# adapter_v2.net
KiCad netlist of a schematic drawn in EAGLE
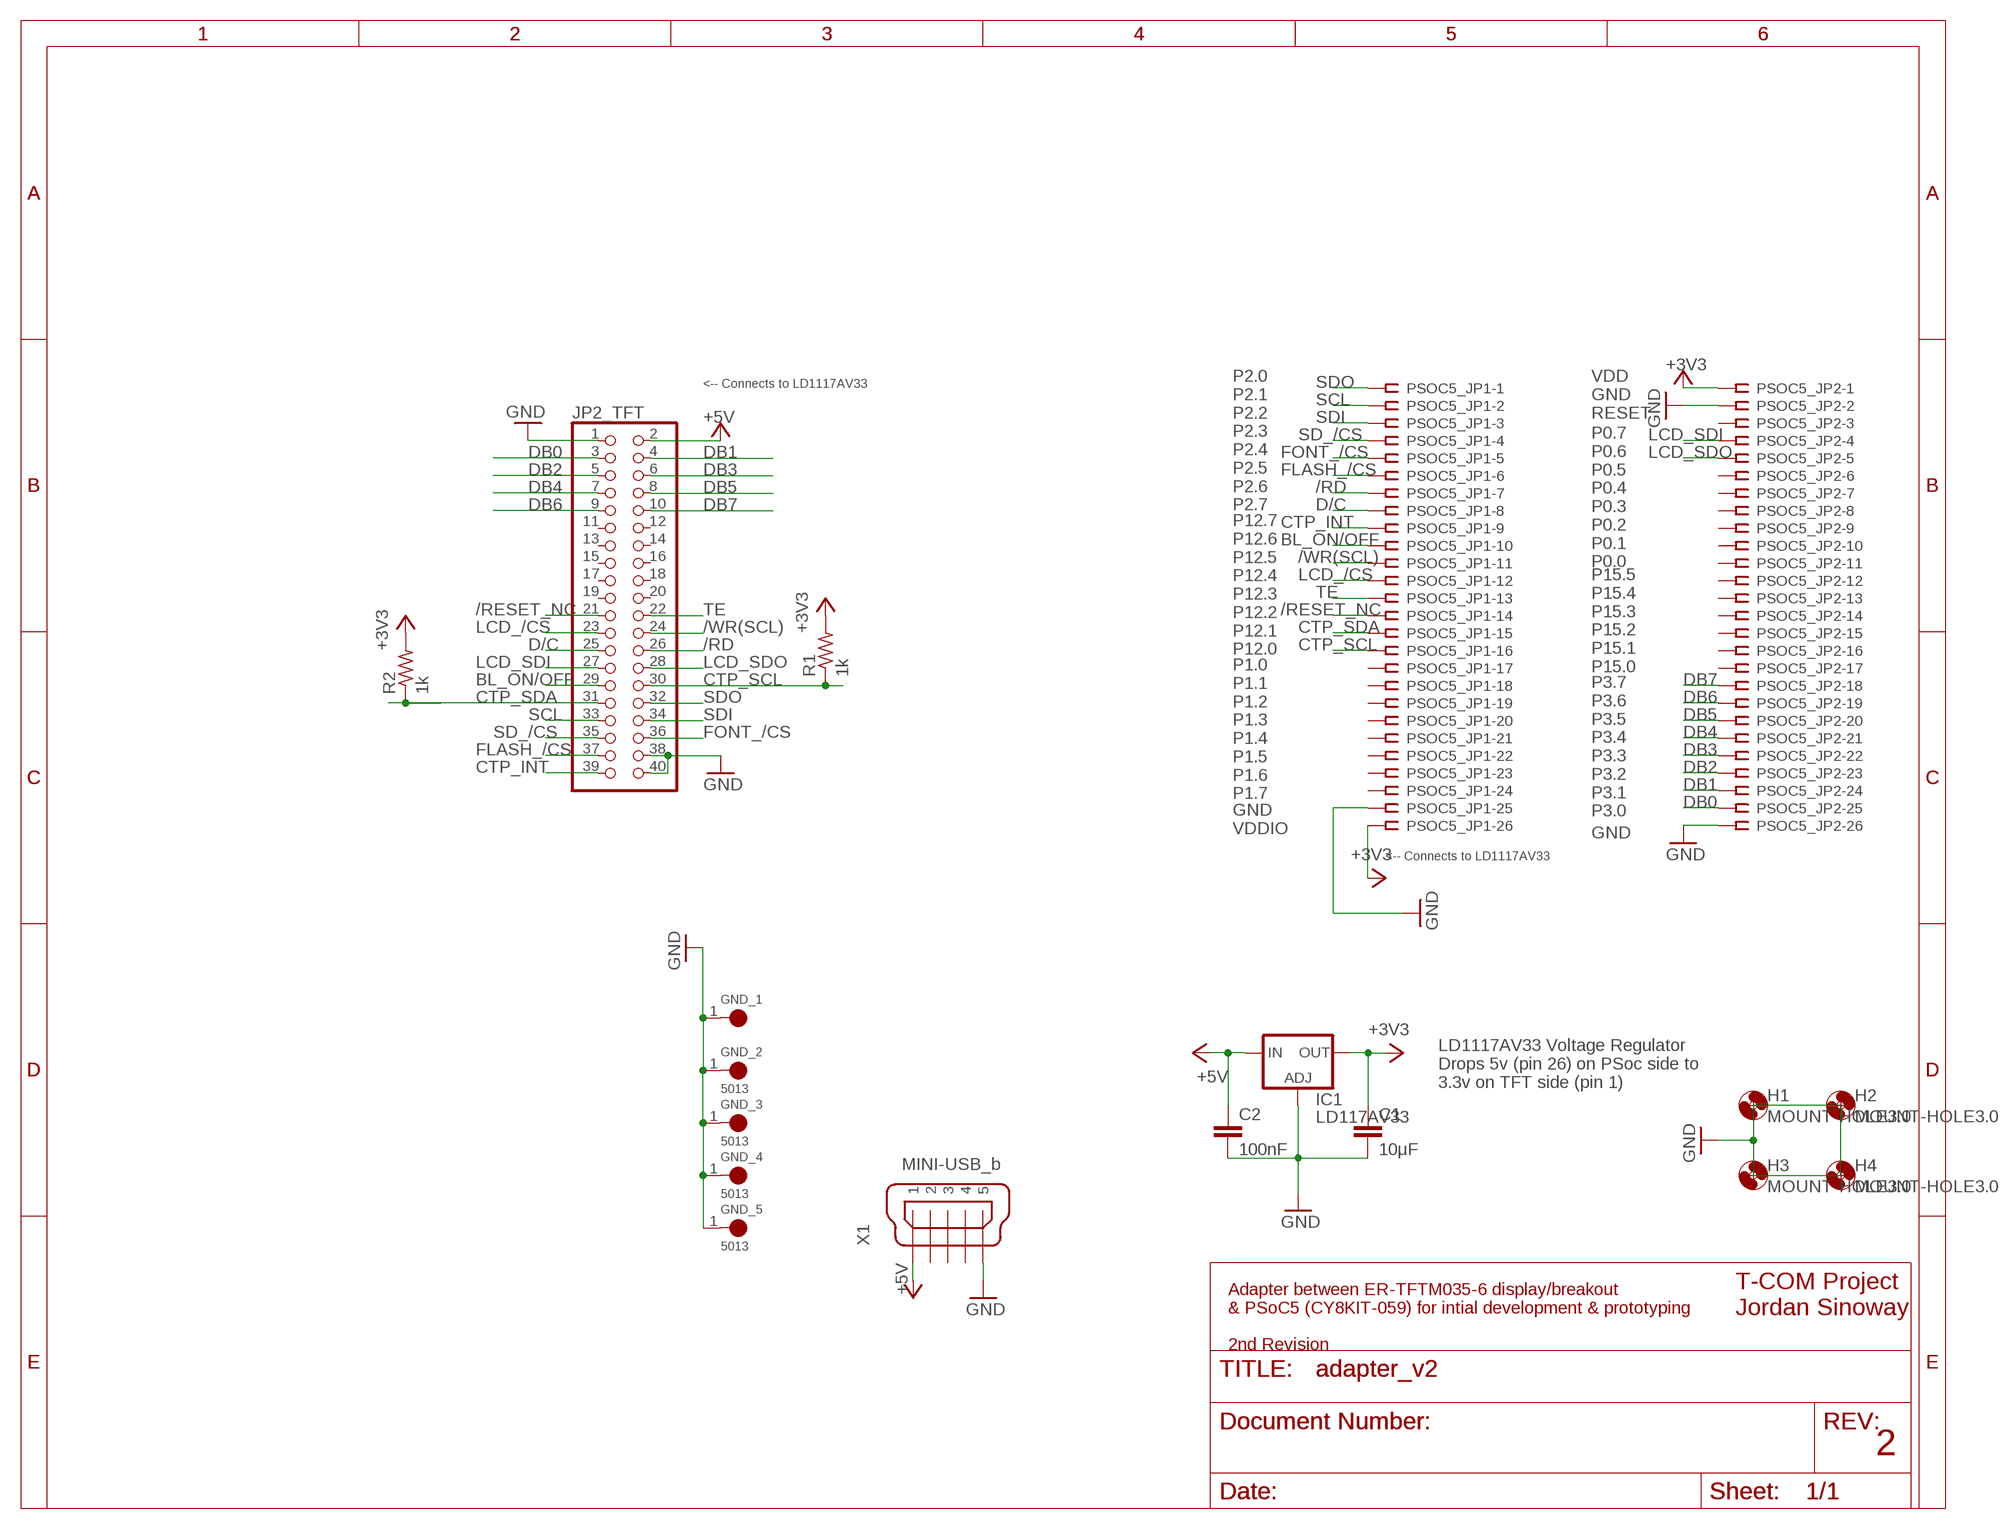
[diagram p0: schematic, sheet 1]

(export (version "E")
  (design (tool "Eeschema 10.0.6"))
  (components
    (comp (ref "C1")
      (value "10μF")
      (footprint "eagle-import:C2.5-2")
      (libsource (lib "eagle-import") (part "C2.5/2"))
    )
    (comp (ref "C2")
      (value "100nF")
      (footprint "eagle-import:C2.5-2")
      (libsource (lib "eagle-import") (part "C2.5/2"))
    )
    (comp (ref "GND_1")
      (value "5013")
      (footprint "eagle-import:TESTPOINT_5013")
      (fields (field (name "MF") "Keystone Electronics"))
      (libsource (lib "eagle-import") (part "5013"))
    )
    (comp (ref "GND_2")
      (value "5013")
      (footprint "eagle-import:TESTPOINT_5013")
      (fields (field (name "MF") "Keystone Electronics"))
      (libsource (lib "eagle-import") (part "5013"))
    )
    (comp (ref "GND_3")
      (value "5013")
      (footprint "eagle-import:TESTPOINT_5013")
      (fields (field (name "MF") "Keystone Electronics"))
      (libsource (lib "eagle-import") (part "5013"))
    )
    (comp (ref "GND_4")
      (value "5013")
      (footprint "eagle-import:TESTPOINT_5013")
      (fields (field (name "MF") "Keystone Electronics"))
      (libsource (lib "eagle-import") (part "5013"))
    )
    (comp (ref "GND_5")
      (value "5013")
      (footprint "eagle-import:TESTPOINT_5013")
      (fields (field (name "MF") "Keystone Electronics"))
      (libsource (lib "eagle-import") (part "5013"))
    )
    (comp (ref "H1")
      (value "MOUNT-HOLE3.0")
      (footprint "eagle-import:3,0")
      (libsource (lib "eagle-import") (part "MOUNT-HOLE3.0"))
    )
    (comp (ref "H2")
      (value "MOUNT-HOLE3.0")
      (footprint "eagle-import:3,0")
      (libsource (lib "eagle-import") (part "MOUNT-HOLE3.0"))
    )
    (comp (ref "H3")
      (value "MOUNT-HOLE3.0")
      (footprint "eagle-import:3,0")
      (libsource (lib "eagle-import") (part "MOUNT-HOLE3.0"))
    )
    (comp (ref "H4")
      (value "MOUNT-HOLE3.0")
      (footprint "eagle-import:3,0")
      (libsource (lib "eagle-import") (part "MOUNT-HOLE3.0"))
    )
    (comp (ref "IC1")
      (value "LD117AV33")
      (footprint "eagle-import:TO220L1")
      (libsource (lib "eagle-import") (part "LD117A?V33"))
    )
    (comp (ref "JP2_TFT")
      (value "PINHD-2X20")
      (footprint "eagle-import:2X20")
      (libsource (lib "eagle-import") (part "PINHD-2X20"))
    )
    (comp (ref "PSOC5_JP1")
      (value "SSW-126-02-G-S")
      (footprint "eagle-import:SSW-126-02-G-S")
      (fields (field (name "MF") "Samtec Inc."))
      (libsource (lib "eagle-import") (part "SSW-126-02-G-S"))
    )
    (comp (ref "PSOC5_JP2")
      (value "SSW-126-02-G-S")
      (footprint "eagle-import:SSW-126-02-G-S")
      (fields (field (name "MF") "Samtec Inc."))
      (libsource (lib "eagle-import") (part "SSW-126-02-G-S"))
    )
    (comp (ref "R1")
      (value "1k")
      (footprint "eagle-import:0204_7")
      (libsource (lib "eagle-import") (part "R-US_0204/7"))
    )
    (comp (ref "R2")
      (value "1k")
      (footprint "eagle-import:0204_7")
      (libsource (lib "eagle-import") (part "R-US_0204/7"))
    )
    (comp (ref "X1")
      (value "MINI-USB_b")
      (footprint "eagle-import:32005-601")
      (libsource (lib "eagle-import") (part "MINI-USB_SHIELD5P2-32005-601"))
    )
  )
  (nets
    (net (code "1") (name "+3V3") (class "Default")
      (node (ref "C1") (pin "1") (pinfunction "1_1") (pintype "passive"))
      (node (ref "IC1") (pin "2") (pinfunction "OUT_2") (pintype "passive"))
      (node (ref "PSOC5_JP1") (pin "26") (pinfunction "1_26") (pintype "passive"))
      (node (ref "PSOC5_JP2") (pin "1") (pinfunction "1_1") (pintype "passive"))
      (node (ref "R1") (pin "2") (pinfunction "2_2") (pintype "passive"))
      (node (ref "R2") (pin "2") (pinfunction "2_2") (pintype "passive"))
    )
    (net (code "2") (name "+5V") (class "Default")
      (node (ref "C2") (pin "1") (pinfunction "1_1") (pintype "passive"))
      (node (ref "IC1") (pin "3") (pinfunction "IN_3") (pintype "input"))
      (node (ref "JP2_TFT") (pin "2") (pinfunction "2_2") (pintype "passive"))
      (node (ref "X1") (pin "1") (pinfunction "1_1") (pintype "passive"))
    )
    (net (code "3") (name "/BL_ON{slash}OFF") (class "Default")
      (node (ref "JP2_TFT") (pin "29") (pinfunction "29_29") (pintype "passive"))
      (node (ref "PSOC5_JP1") (pin "10") (pinfunction "1_10") (pintype "passive"))
    )
    (net (code "4") (name "/CTP_INT") (class "Default")
      (node (ref "JP2_TFT") (pin "39") (pinfunction "39_39") (pintype "passive"))
      (node (ref "PSOC5_JP1") (pin "9") (pinfunction "1_9") (pintype "passive"))
    )
    (net (code "5") (name "/CTP_SCL") (class "Default")
      (node (ref "JP2_TFT") (pin "30") (pinfunction "30_30") (pintype "passive"))
      (node (ref "PSOC5_JP1") (pin "16") (pinfunction "1_16") (pintype "passive"))
      (node (ref "R1") (pin "1") (pinfunction "1_1") (pintype "passive"))
    )
    (net (code "6") (name "/CTP_SDA") (class "Default")
      (node (ref "JP2_TFT") (pin "31") (pinfunction "31_31") (pintype "passive"))
      (node (ref "PSOC5_JP1") (pin "15") (pinfunction "1_15") (pintype "passive"))
      (node (ref "R2") (pin "1") (pinfunction "1_1") (pintype "passive"))
    )
    (net (code "7") (name "/DB0") (class "Default")
      (node (ref "JP2_TFT") (pin "3") (pinfunction "3_3") (pintype "passive"))
      (node (ref "PSOC5_JP2") (pin "25") (pinfunction "1_25") (pintype "passive"))
    )
    (net (code "8") (name "/DB1") (class "Default")
      (node (ref "JP2_TFT") (pin "4") (pinfunction "4_4") (pintype "passive"))
      (node (ref "PSOC5_JP2") (pin "24") (pinfunction "1_24") (pintype "passive"))
    )
    (net (code "9") (name "/DB2") (class "Default")
      (node (ref "JP2_TFT") (pin "5") (pinfunction "5_5") (pintype "passive"))
      (node (ref "PSOC5_JP2") (pin "23") (pinfunction "1_23") (pintype "passive"))
    )
    (net (code "10") (name "/DB3") (class "Default")
      (node (ref "JP2_TFT") (pin "6") (pinfunction "6_6") (pintype "passive"))
      (node (ref "PSOC5_JP2") (pin "22") (pinfunction "1_22") (pintype "passive"))
    )
    (net (code "11") (name "/DB4") (class "Default")
      (node (ref "JP2_TFT") (pin "7") (pinfunction "7_7") (pintype "passive"))
      (node (ref "PSOC5_JP2") (pin "21") (pinfunction "1_21") (pintype "passive"))
    )
    (net (code "12") (name "/DB5") (class "Default")
      (node (ref "JP2_TFT") (pin "8") (pinfunction "8_8") (pintype "passive"))
      (node (ref "PSOC5_JP2") (pin "20") (pinfunction "1_20") (pintype "passive"))
    )
    (net (code "13") (name "/DB6") (class "Default")
      (node (ref "JP2_TFT") (pin "9") (pinfunction "9_9") (pintype "passive"))
      (node (ref "PSOC5_JP2") (pin "19") (pinfunction "1_19") (pintype "passive"))
    )
    (net (code "14") (name "/DB7") (class "Default")
      (node (ref "JP2_TFT") (pin "10") (pinfunction "10_10") (pintype "passive"))
      (node (ref "PSOC5_JP2") (pin "18") (pinfunction "1_18") (pintype "passive"))
    )
    (net (code "15") (name "/D{slash}C") (class "Default")
      (node (ref "JP2_TFT") (pin "25") (pinfunction "25_25") (pintype "passive"))
      (node (ref "PSOC5_JP1") (pin "8") (pinfunction "1_8") (pintype "passive"))
    )
    (net (code "16") (name "/FLASH_{slash}CS") (class "Default")
      (node (ref "JP2_TFT") (pin "37") (pinfunction "37_37") (pintype "passive"))
      (node (ref "PSOC5_JP1") (pin "6") (pinfunction "1_6") (pintype "passive"))
    )
    (net (code "17") (name "/FONT_{slash}CS") (class "Default")
      (node (ref "JP2_TFT") (pin "36") (pinfunction "36_36") (pintype "passive"))
      (node (ref "PSOC5_JP1") (pin "5") (pinfunction "1_5") (pintype "passive"))
    )
    (net (code "18") (name "/LCD_SDI") (class "Default")
      (node (ref "JP2_TFT") (pin "27") (pinfunction "27_27") (pintype "passive"))
      (node (ref "PSOC5_JP2") (pin "4") (pinfunction "1_4") (pintype "passive"))
    )
    (net (code "19") (name "/LCD_SDO") (class "Default")
      (node (ref "JP2_TFT") (pin "28") (pinfunction "28_28") (pintype "passive"))
      (node (ref "PSOC5_JP2") (pin "5") (pinfunction "1_5") (pintype "passive"))
    )
    (net (code "20") (name "/LCD_{slash}CS") (class "Default")
      (node (ref "JP2_TFT") (pin "23") (pinfunction "23_23") (pintype "passive"))
      (node (ref "PSOC5_JP1") (pin "12") (pinfunction "1_12") (pintype "passive"))
    )
    (net (code "21") (name "/SCL") (class "Default")
      (node (ref "JP2_TFT") (pin "33") (pinfunction "33_33") (pintype "passive"))
      (node (ref "PSOC5_JP1") (pin "2") (pinfunction "1_2") (pintype "passive"))
    )
    (net (code "22") (name "/SDI") (class "Default")
      (node (ref "JP2_TFT") (pin "34") (pinfunction "34_34") (pintype "passive"))
      (node (ref "PSOC5_JP1") (pin "3") (pinfunction "1_3") (pintype "passive"))
    )
    (net (code "23") (name "/SDO") (class "Default")
      (node (ref "JP2_TFT") (pin "32") (pinfunction "32_32") (pintype "passive"))
      (node (ref "PSOC5_JP1") (pin "1") (pinfunction "1_1") (pintype "passive"))
    )
    (net (code "24") (name "/SD_{slash}CS") (class "Default")
      (node (ref "JP2_TFT") (pin "35") (pinfunction "35_35") (pintype "passive"))
      (node (ref "PSOC5_JP1") (pin "4") (pinfunction "1_4") (pintype "passive"))
    )
    (net (code "25") (name "/TE") (class "Default")
      (node (ref "JP2_TFT") (pin "22") (pinfunction "22_22") (pintype "passive"))
      (node (ref "PSOC5_JP1") (pin "13") (pinfunction "1_13") (pintype "passive"))
    )
    (net (code "26") (name "/{slash}RD") (class "Default")
      (node (ref "JP2_TFT") (pin "26") (pinfunction "26_26") (pintype "passive"))
      (node (ref "PSOC5_JP1") (pin "7") (pinfunction "1_7") (pintype "passive"))
    )
    (net (code "27") (name "/{slash}RESET_NC") (class "Default")
      (node (ref "JP2_TFT") (pin "21") (pinfunction "21_21") (pintype "passive"))
      (node (ref "PSOC5_JP1") (pin "14") (pinfunction "1_14") (pintype "passive"))
    )
    (net (code "28") (name "/{slash}WR(SCL)") (class "Default")
      (node (ref "JP2_TFT") (pin "24") (pinfunction "24_24") (pintype "passive"))
      (node (ref "PSOC5_JP1") (pin "11") (pinfunction "1_11") (pintype "passive"))
    )
    (net (code "29") (name "GND") (class "Default")
      (node (ref "C1") (pin "2") (pinfunction "2_2") (pintype "passive"))
      (node (ref "C2") (pin "2") (pinfunction "2_2") (pintype "passive"))
      (node (ref "GND_1") (pin "1") (pinfunction "TP_1") (pintype "passive"))
      (node (ref "GND_2") (pin "1") (pinfunction "TP_1") (pintype "passive"))
      (node (ref "GND_3") (pin "1") (pinfunction "TP_1") (pintype "passive"))
      (node (ref "GND_4") (pin "1") (pinfunction "TP_1") (pintype "passive"))
      (node (ref "GND_5") (pin "1") (pinfunction "TP_1") (pintype "passive"))
      (node (ref "IC1") (pin "1") (pinfunction "ADJ_1") (pintype "input"))
      (node (ref "JP2_TFT") (pin "1") (pinfunction "1_1") (pintype "passive"))
      (node (ref "JP2_TFT") (pin "38") (pinfunction "38_38") (pintype "passive"))
      (node (ref "JP2_TFT") (pin "40") (pinfunction "40_40") (pintype "passive"))
      (node (ref "PSOC5_JP1") (pin "25") (pinfunction "1_25") (pintype "passive"))
      (node (ref "PSOC5_JP2") (pin "2") (pinfunction "1_2") (pintype "passive"))
      (node (ref "PSOC5_JP2") (pin "26") (pinfunction "1_26") (pintype "passive"))
      (node (ref "X1") (pin "5") (pinfunction "5_5") (pintype "passive"))
    )
    (net (code "30") (name "unconnected-(JP2_TFT-Pad11)") (class "Default")
      (node (ref "JP2_TFT") (pin "11") (pinfunction "11_11") (pintype "passive"))
    )
    (net (code "31") (name "unconnected-(JP2_TFT-Pad12)") (class "Default")
      (node (ref "JP2_TFT") (pin "12") (pinfunction "12_12") (pintype "passive"))
    )
    (net (code "32") (name "unconnected-(JP2_TFT-Pad13)") (class "Default")
      (node (ref "JP2_TFT") (pin "13") (pinfunction "13_13") (pintype "passive"))
    )
    (net (code "33") (name "unconnected-(JP2_TFT-Pad14)") (class "Default")
      (node (ref "JP2_TFT") (pin "14") (pinfunction "14_14") (pintype "passive"))
    )
    (net (code "34") (name "unconnected-(JP2_TFT-Pad15)") (class "Default")
      (node (ref "JP2_TFT") (pin "15") (pinfunction "15_15") (pintype "passive"))
    )
    (net (code "35") (name "unconnected-(JP2_TFT-Pad16)") (class "Default")
      (node (ref "JP2_TFT") (pin "16") (pinfunction "16_16") (pintype "passive"))
    )
    (net (code "36") (name "unconnected-(JP2_TFT-Pad17)") (class "Default")
      (node (ref "JP2_TFT") (pin "17") (pinfunction "17_17") (pintype "passive"))
    )
    (net (code "37") (name "unconnected-(JP2_TFT-Pad18)") (class "Default")
      (node (ref "JP2_TFT") (pin "18") (pinfunction "18_18") (pintype "passive"))
    )
    (net (code "38") (name "unconnected-(JP2_TFT-Pad19)") (class "Default")
      (node (ref "JP2_TFT") (pin "19") (pinfunction "19_19") (pintype "passive"))
    )
    (net (code "39") (name "unconnected-(JP2_TFT-Pad20)") (class "Default")
      (node (ref "JP2_TFT") (pin "20") (pinfunction "20_20") (pintype "passive"))
    )
    (net (code "40") (name "unconnected-(PSOC5_JP1I-1-Pad17)") (class "Default")
      (node (ref "PSOC5_JP1") (pin "17") (pinfunction "1_17") (pintype "passive"))
    )
    (net (code "41") (name "unconnected-(PSOC5_JP1J-1-Pad18)") (class "Default")
      (node (ref "PSOC5_JP1") (pin "18") (pinfunction "1_18") (pintype "passive"))
    )
    (net (code "42") (name "unconnected-(PSOC5_JP1K-1-Pad19)") (class "Default")
      (node (ref "PSOC5_JP1") (pin "19") (pinfunction "1_19") (pintype "passive"))
    )
    (net (code "43") (name "unconnected-(PSOC5_JP1M-1-Pad20)") (class "Default")
      (node (ref "PSOC5_JP1") (pin "20") (pinfunction "1_20") (pintype "passive"))
    )
    (net (code "44") (name "unconnected-(PSOC5_JP1N-1-Pad21)") (class "Default")
      (node (ref "PSOC5_JP1") (pin "21") (pinfunction "1_21") (pintype "passive"))
    )
    (net (code "45") (name "unconnected-(PSOC5_JP1O-1-Pad22)") (class "Default")
      (node (ref "PSOC5_JP1") (pin "22") (pinfunction "1_22") (pintype "passive"))
    )
    (net (code "46") (name "unconnected-(PSOC5_JP1P-1-Pad23)") (class "Default")
      (node (ref "PSOC5_JP1") (pin "23") (pinfunction "1_23") (pintype "passive"))
    )
    (net (code "47") (name "unconnected-(PSOC5_JP1Q-1-Pad24)") (class "Default")
      (node (ref "PSOC5_JP1") (pin "24") (pinfunction "1_24") (pintype "passive"))
    )
    (net (code "48") (name "unconnected-(PSOC5_JP2B-1-Pad10)") (class "Default")
      (node (ref "PSOC5_JP2") (pin "10") (pinfunction "1_10") (pintype "passive"))
    )
    (net (code "49") (name "unconnected-(PSOC5_JP2C-1-Pad11)") (class "Default")
      (node (ref "PSOC5_JP2") (pin "11") (pinfunction "1_11") (pintype "passive"))
    )
    (net (code "50") (name "unconnected-(PSOC5_JP2D-1-Pad12)") (class "Default")
      (node (ref "PSOC5_JP2") (pin "12") (pinfunction "1_12") (pintype "passive"))
    )
    (net (code "51") (name "unconnected-(PSOC5_JP2E-1-Pad13)") (class "Default")
      (node (ref "PSOC5_JP2") (pin "13") (pinfunction "1_13") (pintype "passive"))
    )
    (net (code "52") (name "unconnected-(PSOC5_JP2F-1-Pad14)") (class "Default")
      (node (ref "PSOC5_JP2") (pin "14") (pinfunction "1_14") (pintype "passive"))
    )
    (net (code "53") (name "unconnected-(PSOC5_JP2G-1-Pad15)") (class "Default")
      (node (ref "PSOC5_JP2") (pin "15") (pinfunction "1_15") (pintype "passive"))
    )
    (net (code "54") (name "unconnected-(PSOC5_JP2H-1-Pad16)") (class "Default")
      (node (ref "PSOC5_JP2") (pin "16") (pinfunction "1_16") (pintype "passive"))
    )
    (net (code "55") (name "unconnected-(PSOC5_JP2I-1-Pad17)") (class "Default")
      (node (ref "PSOC5_JP2") (pin "17") (pinfunction "1_17") (pintype "passive"))
    )
    (net (code "56") (name "unconnected-(PSOC5_JP2T-1-Pad3)") (class "Default")
      (node (ref "PSOC5_JP2") (pin "3") (pinfunction "1_3") (pintype "passive"))
    )
    (net (code "57") (name "unconnected-(PSOC5_JP2W-1-Pad6)") (class "Default")
      (node (ref "PSOC5_JP2") (pin "6") (pinfunction "1_6") (pintype "passive"))
    )
    (net (code "58") (name "unconnected-(PSOC5_JP2X-1-Pad7)") (class "Default")
      (node (ref "PSOC5_JP2") (pin "7") (pinfunction "1_7") (pintype "passive"))
    )
    (net (code "59") (name "unconnected-(PSOC5_JP2Y-1-Pad8)") (class "Default")
      (node (ref "PSOC5_JP2") (pin "8") (pinfunction "1_8") (pintype "passive"))
    )
    (net (code "60") (name "unconnected-(PSOC5_JP2Z-1-Pad9)") (class "Default")
      (node (ref "PSOC5_JP2") (pin "9") (pinfunction "1_9") (pintype "passive"))
    )
    (net (code "61") (name "unconnected-(X1-Pad2)") (class "Default")
      (node (ref "X1") (pin "2") (pinfunction "2_2") (pintype "passive"))
    )
    (net (code "62") (name "unconnected-(X1-Pad3)") (class "Default")
      (node (ref "X1") (pin "3") (pinfunction "3_3") (pintype "passive"))
    )
    (net (code "63") (name "unconnected-(X1-Pad4)") (class "Default")
      (node (ref "X1") (pin "4") (pinfunction "4_4") (pintype "passive"))
    )
  )
)
